# SENSOR.net
KiCad netlist of a schematic drawn in Altium Designer
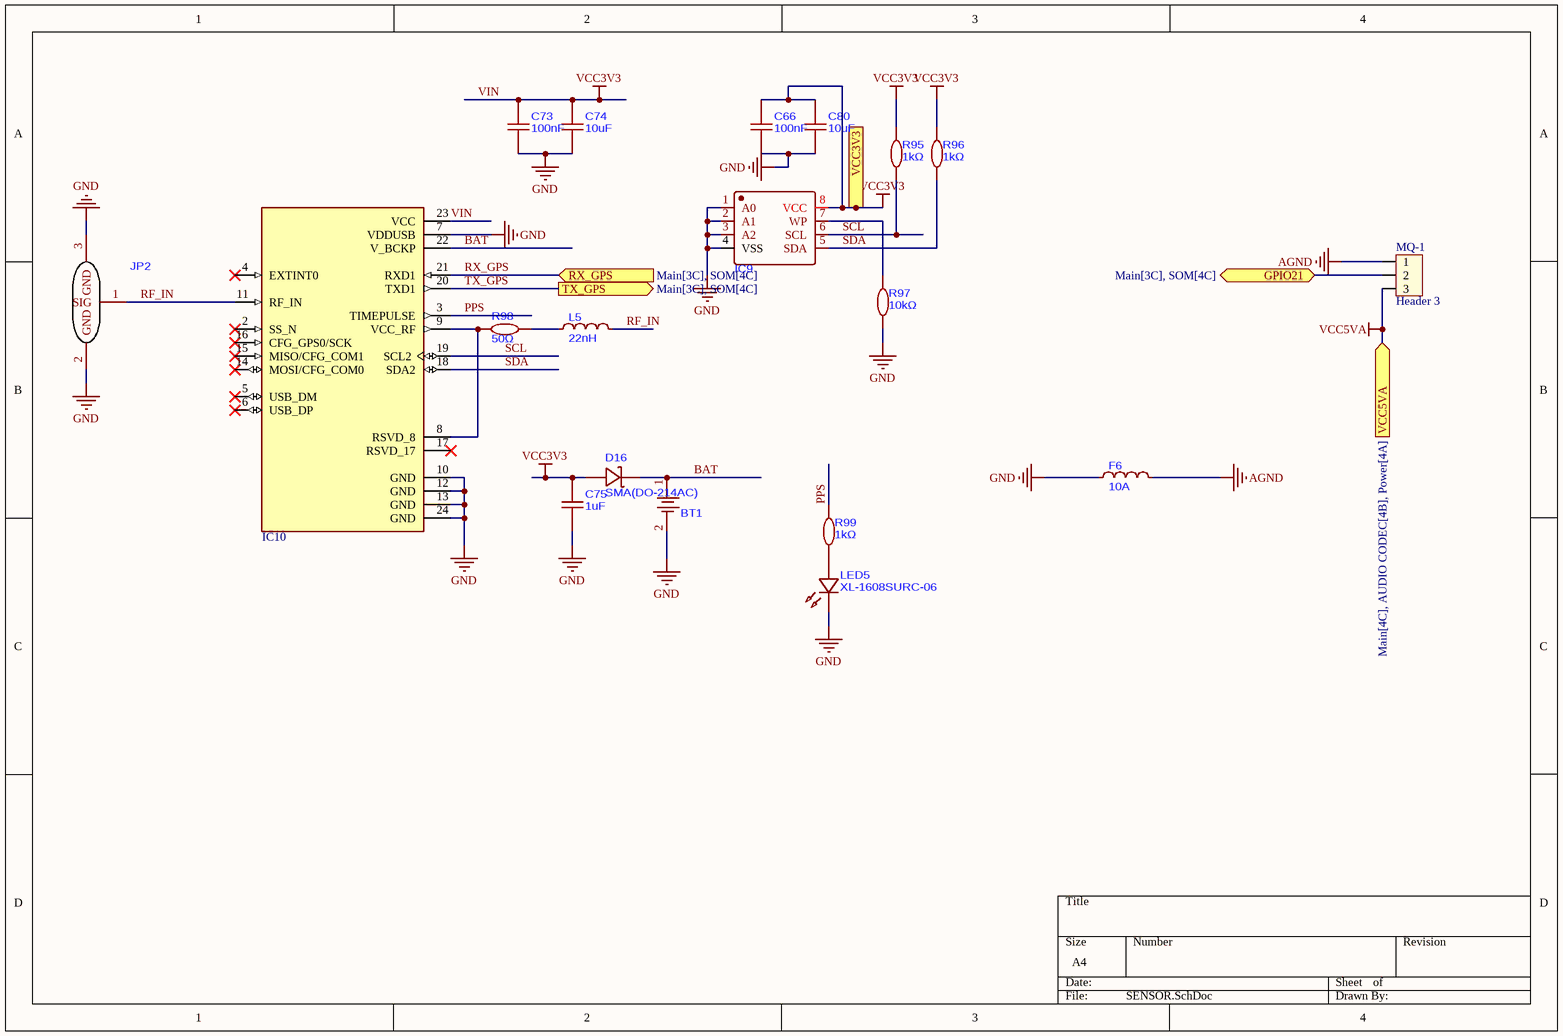
[diagram p0: SENSOR.SchDoc]

(export (version "E")
  (design (tool "Eeschema 10.0.6"))
  (components
    (comp (ref "BT1")
      (value "BATTERY CLIP COIN CR2032 SMD")
      (footprint "BATTERY")
      (description "Battery Clip CR2032 SMD Blade Type Power Connector Assemblies RoHS")
      (libsource (lib "Schlib2") (part "C70373"))
    )
    (comp (ref "C66")
      (value "100nF")
      (footprint "C0603")
      (description "50V 100nF X7R ±10% 0603 Ceramic Capacitors ROHS")
      (libsource (lib "Schlib2") (part "CC0603KRX7R9BB104"))
    )
    (comp (ref "C73")
      (value "100nF")
      (footprint "C0603")
      (description "50V 100nF X7R ±10% 0603 Ceramic Capacitors ROHS")
      (libsource (lib "Schlib2") (part "CC0603KRX7R9BB104"))
    )
    (comp (ref "C74")
      (value "10uF")
      (footprint "C0603")
      (description "25V 10uF X5R ±20% 0603 Ceramic Capacitors ROHS")
      (libsource (lib "Schlib2") (part "CL10A106MA8NRNC"))
    )
    (comp (ref "C75")
      (value "1uF")
      (footprint "C0603")
      (description "25V 1uF X7R ±10% 0603 Ceramic Capacitors ROHS")
      (libsource (lib "Schlib2") (part "CL10B105KA8NNNC"))
    )
    (comp (ref "C80")
      (value "10uF")
      (footprint "C0603")
      (description "25V 10uF X5R ±20% 0603 Ceramic Capacitors ROHS")
      (libsource (lib "Schlib2") (part "CL10A106MA8NRNC"))
    )
    (comp (ref "D16")
      (value "SMA(DO-214AC)")
      (footprint "SMA_L4.4-W2.6-LS5.0-RD")
      (description "80A 40V 500mV@3A 3A SMA(DO-214AC) Single Diodes ROHS")
      (libsource (lib "Schlib2") (part "B340A-13-F"))
    )
    (comp (ref "F6")
      (value "10A")
      (footprint "IND-SMD_L8.5-W3.1")
      (description "4mΩ 100Ω@100MHz SMD,8.5x3.1mm Ferrite Beads and Chips ROHS")
      (libsource (lib "Schlib2") (part "HI3312X101R-10"))
    )
    (comp (ref "IC9")
      (value "256 kb Serial CMOS EEPROM with I2C Protocol")
      (footprint "SOIC-8_L4.9-W3.9-P1.27-LS6.0-BL")
      (description "256Kbit 1.8V~5.5V 1MHz I2C SOIC-8 Memory (ICs) RoHS")
      (libsource (lib "Schlib2") (part "CAT24C256WI-GT3"))
    )
    (comp (ref "IC10")
      (value "GPS NEO 6")
      (footprint "XCVR_NEO-6M-GPS")
      (description "GPS Development Tools SparkFun GNSS-RTK Dead Reckoning Breakout - ZED-F9K (Qwiic)")
      (fields (field (name "MP") "NEO-6M-GPS") (field (name "MF") "u-blox"))
      (libsource (lib "Schlib2") (part "NEO-6M-GPS"))
    )
    (comp (ref "JP2")
      (value "CONN RCPT IPEX 50Ω SMD")
      (footprint "RF-SMD_FRF05002-JSS103M")
      (libsource (lib "Schlib2") (part "U.FL-R-SMT-1(80)"))
    )
    (comp (ref "L5")
      (value "22nH")
      (footprint "C0603")
      (description "300mA 22nH ±5% 600mΩ 0603 Fixed Inductors RoHS")
      (libsource (lib "Schlib2") (part "VHF160808H22NJT"))
    )
    (comp (ref "LED5")
      (value "XL-1608SURC-06")
      (footprint "LED0603-RD_RED")
      (description "20mA 2.3V Red 50mW 0603 LED Indication - Discrete ROHS")
      (libsource (lib "Schlib2") (part "XL-1608SURC-06"))
    )
    (comp (ref "MQ-1")
      (value "Header 3")
      (footprint "HED3")
      (description "Header 3 (Green)")
      (libsource (lib "syhaunguyen") (part "Hed3"))
    )
    (comp (ref "R95")
      (value "1kΩ")
      (footprint "R0603")
      (description "100mW 1kΩ 50V ±100ppm/℃ Thick Film Resistor ±5% 0603 Chip Resistor - Surface Mount ROHS")
      (libsource (lib "Schlib2") (part "RMC 0603 1K J N"))
    )
    (comp (ref "R96")
      (value "1kΩ")
      (footprint "R0603")
      (description "100mW 1kΩ 50V ±100ppm/℃ Thick Film Resistor ±5% 0603 Chip Resistor - Surface Mount ROHS")
      (libsource (lib "Schlib2") (part "RMC 0603 1K J N"))
    )
    (comp (ref "R97")
      (value "10kΩ")
      (footprint "R0603")
      (description "100mW 10kΩ 75V ±100ppm/℃ Thick Film Resistor ±1% 0603 Chip Resistor - Surface Mount ROHS")
      (libsource (lib "Schlib2") (part "RC0603FR-0710KL"))
    )
    (comp (ref "R98")
      (value "50Ω")
      (footprint "R0603")
      (description "100mW 50Ω 75V ±50ppm/℃ Thin Film Resistor ±0.1% 0603 Chip Resistor - Surface Mount ROHS")
      (libsource (lib "Schlib2") (part "RT0603BRE0750RL"))
    )
    (comp (ref "R99")
      (value "1kΩ")
      (footprint "R0603")
      (description "100mW 1kΩ 50V ±100ppm/℃ Thick Film Resistor ±5% 0603 Chip Resistor - Surface Mount ROHS")
      (libsource (lib "Schlib2") (part "RMC 0603 1K J N"))
    )
  )
  (nets
    (net (code "1") (name "/BAT") (class "Default")
      (node (ref "BT1") (pin "1") (pinfunction "1_1") (pintype "passive"))
      (node (ref "D16") (pin "1") (pinfunction "K_1") (pintype "passive"))
      (node (ref "IC10") (pin "22") (pinfunction "V_BCKP_22") (pintype "power_in"))
    )
    (net (code "2") (name "/GPIO21") (class "Default")
      (node (ref "MQ-1") (pin "2") (pinfunction "2_2") (pintype "passive"))
    )
    (net (code "3") (name "/PPS") (class "Default")
      (node (ref "IC10") (pin "3") (pinfunction "TIMEPULSE_3") (pintype "output"))
      (node (ref "R99") (pin "2") (pinfunction "2_2") (pintype "passive"))
    )
    (net (code "4") (name "/RF_IN") (class "Default")
      (node (ref "IC10") (pin "11") (pinfunction "RF_IN_11") (pintype "input"))
      (node (ref "JP2") (pin "1") (pinfunction "SIG_1") (pintype "passive"))
      (node (ref "L5") (pin "2") (pinfunction "2_2") (pintype "passive"))
    )
    (net (code "5") (name "/RX_GPS") (class "Default")
      (node (ref "IC10") (pin "21") (pinfunction "RXD1_21") (pintype "input"))
    )
    (net (code "6") (name "/SCL") (class "Default")
      (node (ref "IC10") (pin "19") (pinfunction "SCL2_19") (pintype "bidirectional"))
      (node (ref "IC9") (pin "6") (pinfunction "SCL_6") (pintype "passive"))
      (node (ref "R95") (pin "1") (pinfunction "1_1") (pintype "passive"))
    )
    (net (code "7") (name "/SDA") (class "Default")
      (node (ref "IC10") (pin "18") (pinfunction "SDA2_18") (pintype "bidirectional"))
      (node (ref "IC9") (pin "5") (pinfunction "SDA_5") (pintype "passive"))
      (node (ref "R96") (pin "1") (pinfunction "1_1") (pintype "passive"))
    )
    (net (code "8") (name "/TX_GPS") (class "Default")
      (node (ref "IC10") (pin "20") (pinfunction "TXD1_20") (pintype "output"))
    )
    (net (code "9") (name "AGND") (class "Default")
      (node (ref "F6") (pin "2") (pinfunction "2_2") (pintype "passive"))
      (node (ref "MQ-1") (pin "1") (pinfunction "1_1") (pintype "passive"))
    )
    (net (code "10") (name "GND") (class "Default")
      (node (ref "BT1") (pin "2") (pinfunction "2_2") (pintype "passive"))
      (node (ref "C66") (pin "1") (pinfunction "1_1") (pintype "passive"))
      (node (ref "C73") (pin "1") (pinfunction "1_1") (pintype "passive"))
      (node (ref "C74") (pin "1") (pinfunction "1_1") (pintype "passive"))
      (node (ref "C75") (pin "1") (pinfunction "1_1") (pintype "passive"))
      (node (ref "C80") (pin "1") (pinfunction "1_1") (pintype "passive"))
      (node (ref "F6") (pin "1") (pinfunction "1_1") (pintype "passive"))
      (node (ref "IC10") (pin "10") (pinfunction "GND_10") (pintype "power_in"))
      (node (ref "IC10") (pin "12") (pinfunction "GND_12") (pintype "power_in"))
      (node (ref "IC10") (pin "13") (pinfunction "GND_13") (pintype "power_in"))
      (node (ref "IC10") (pin "24") (pinfunction "GND_24") (pintype "power_in"))
      (node (ref "IC10") (pin "7") (pinfunction "VDDUSB_7") (pintype "power_in"))
      (node (ref "IC9") (pin "1") (pinfunction "A0_1") (pintype "passive"))
      (node (ref "IC9") (pin "2") (pinfunction "A1_2") (pintype "passive"))
      (node (ref "IC9") (pin "3") (pinfunction "A2_3") (pintype "passive"))
      (node (ref "IC9") (pin "4") (pinfunction "VSS_4") (pintype "passive"))
      (node (ref "JP2") (pin "2") (pinfunction "GND_2") (pintype "passive"))
      (node (ref "JP2") (pin "3") (pinfunction "GND_3") (pintype "passive"))
      (node (ref "LED5") (pin "1") (pinfunction "K_1") (pintype "passive"))
      (node (ref "R97") (pin "1") (pinfunction "1_1") (pintype "passive"))
    )
    (net (code "11") (name "Net-(IC9-WP)") (class "Default")
      (node (ref "IC9") (pin "7") (pinfunction "WP_7") (pintype "passive"))
      (node (ref "R97") (pin "2") (pinfunction "2_2") (pintype "passive"))
    )
    (net (code "12") (name "Net-(IC10-RSVD_8)") (class "Default")
      (node (ref "IC10") (pin "8") (pinfunction "RSVD_8_8") (pintype "passive"))
      (node (ref "IC10") (pin "9") (pinfunction "VCC_RF_9") (pintype "output"))
      (node (ref "R98") (pin "1") (pinfunction "1_1") (pintype "passive"))
    )
    (net (code "13") (name "Net-(L5-Pad1)") (class "Default")
      (node (ref "L5") (pin "1") (pinfunction "1_1") (pintype "passive"))
      (node (ref "R98") (pin "2") (pinfunction "2_2") (pintype "passive"))
    )
    (net (code "14") (name "Net-(LED5-A)") (class "Default")
      (node (ref "LED5") (pin "2") (pinfunction "A_2") (pintype "passive"))
      (node (ref "R99") (pin "1") (pinfunction "1_1") (pintype "passive"))
    )
    (net (code "15") (name "VCC3V3") (class "Default")
      (node (ref "C66") (pin "2") (pinfunction "2_2") (pintype "passive"))
      (node (ref "C73") (pin "2") (pinfunction "2_2") (pintype "passive"))
      (node (ref "C74") (pin "2") (pinfunction "2_2") (pintype "passive"))
      (node (ref "C75") (pin "2") (pinfunction "2_2") (pintype "passive"))
      (node (ref "C80") (pin "2") (pinfunction "2_2") (pintype "passive"))
      (node (ref "D16") (pin "2") (pinfunction "A_2") (pintype "passive"))
      (node (ref "IC10") (pin "23") (pinfunction "VCC_23") (pintype "passive"))
      (node (ref "IC9") (pin "8") (pinfunction "VCC_8") (pintype "passive"))
      (node (ref "R95") (pin "2") (pinfunction "2_2") (pintype "passive"))
      (node (ref "R96") (pin "2") (pinfunction "2_2") (pintype "passive"))
    )
    (net (code "16") (name "VCC5VA") (class "Default")
      (node (ref "MQ-1") (pin "3") (pinfunction "3_3") (pintype "passive"))
    )
    (net (code "17") (name "unconnected-(IC10-CFG_GPS0{slash}SCK-Pad16)") (class "Default")
      (node (ref "IC10") (pin "16") (pinfunction "CFG_GPS0/SCK_16") (pintype "input+no_connect"))
    )
    (net (code "18") (name "unconnected-(IC10-EXTINT0-Pad4)") (class "Default")
      (node (ref "IC10") (pin "4") (pinfunction "EXTINT0_4") (pintype "input+no_connect"))
    )
    (net (code "19") (name "unconnected-(IC10-MISO{slash}CFG_COM1-Pad15)") (class "Default")
      (node (ref "IC10") (pin "15") (pinfunction "MISO/CFG_COM1_15") (pintype "input+no_connect"))
    )
    (net (code "20") (name "unconnected-(IC10-MOSI{slash}CFG_COM0-Pad14)") (class "Default")
      (node (ref "IC10") (pin "14") (pinfunction "MOSI/CFG_COM0_14") (pintype "bidirectional+no_connect"))
    )
    (net (code "21") (name "unconnected-(IC10-RSVD_17-Pad17)") (class "Default")
      (node (ref "IC10") (pin "17") (pinfunction "RSVD_17_17") (pintype "passive+no_connect"))
    )
    (net (code "22") (name "unconnected-(IC10-SS_N-Pad2)") (class "Default")
      (node (ref "IC10") (pin "2") (pinfunction "SS_N_2") (pintype "input+no_connect"))
    )
    (net (code "23") (name "unconnected-(IC10-USB_DM-Pad5)") (class "Default")
      (node (ref "IC10") (pin "5") (pinfunction "USB_DM_5") (pintype "bidirectional+no_connect"))
    )
    (net (code "24") (name "unconnected-(IC10-USB_DP-Pad6)") (class "Default")
      (node (ref "IC10") (pin "6") (pinfunction "USB_DP_6") (pintype "bidirectional+no_connect"))
    )
  )
)
